# cable-adapter-24.net
KiCad netlist of a schematic drawn in EAGLE
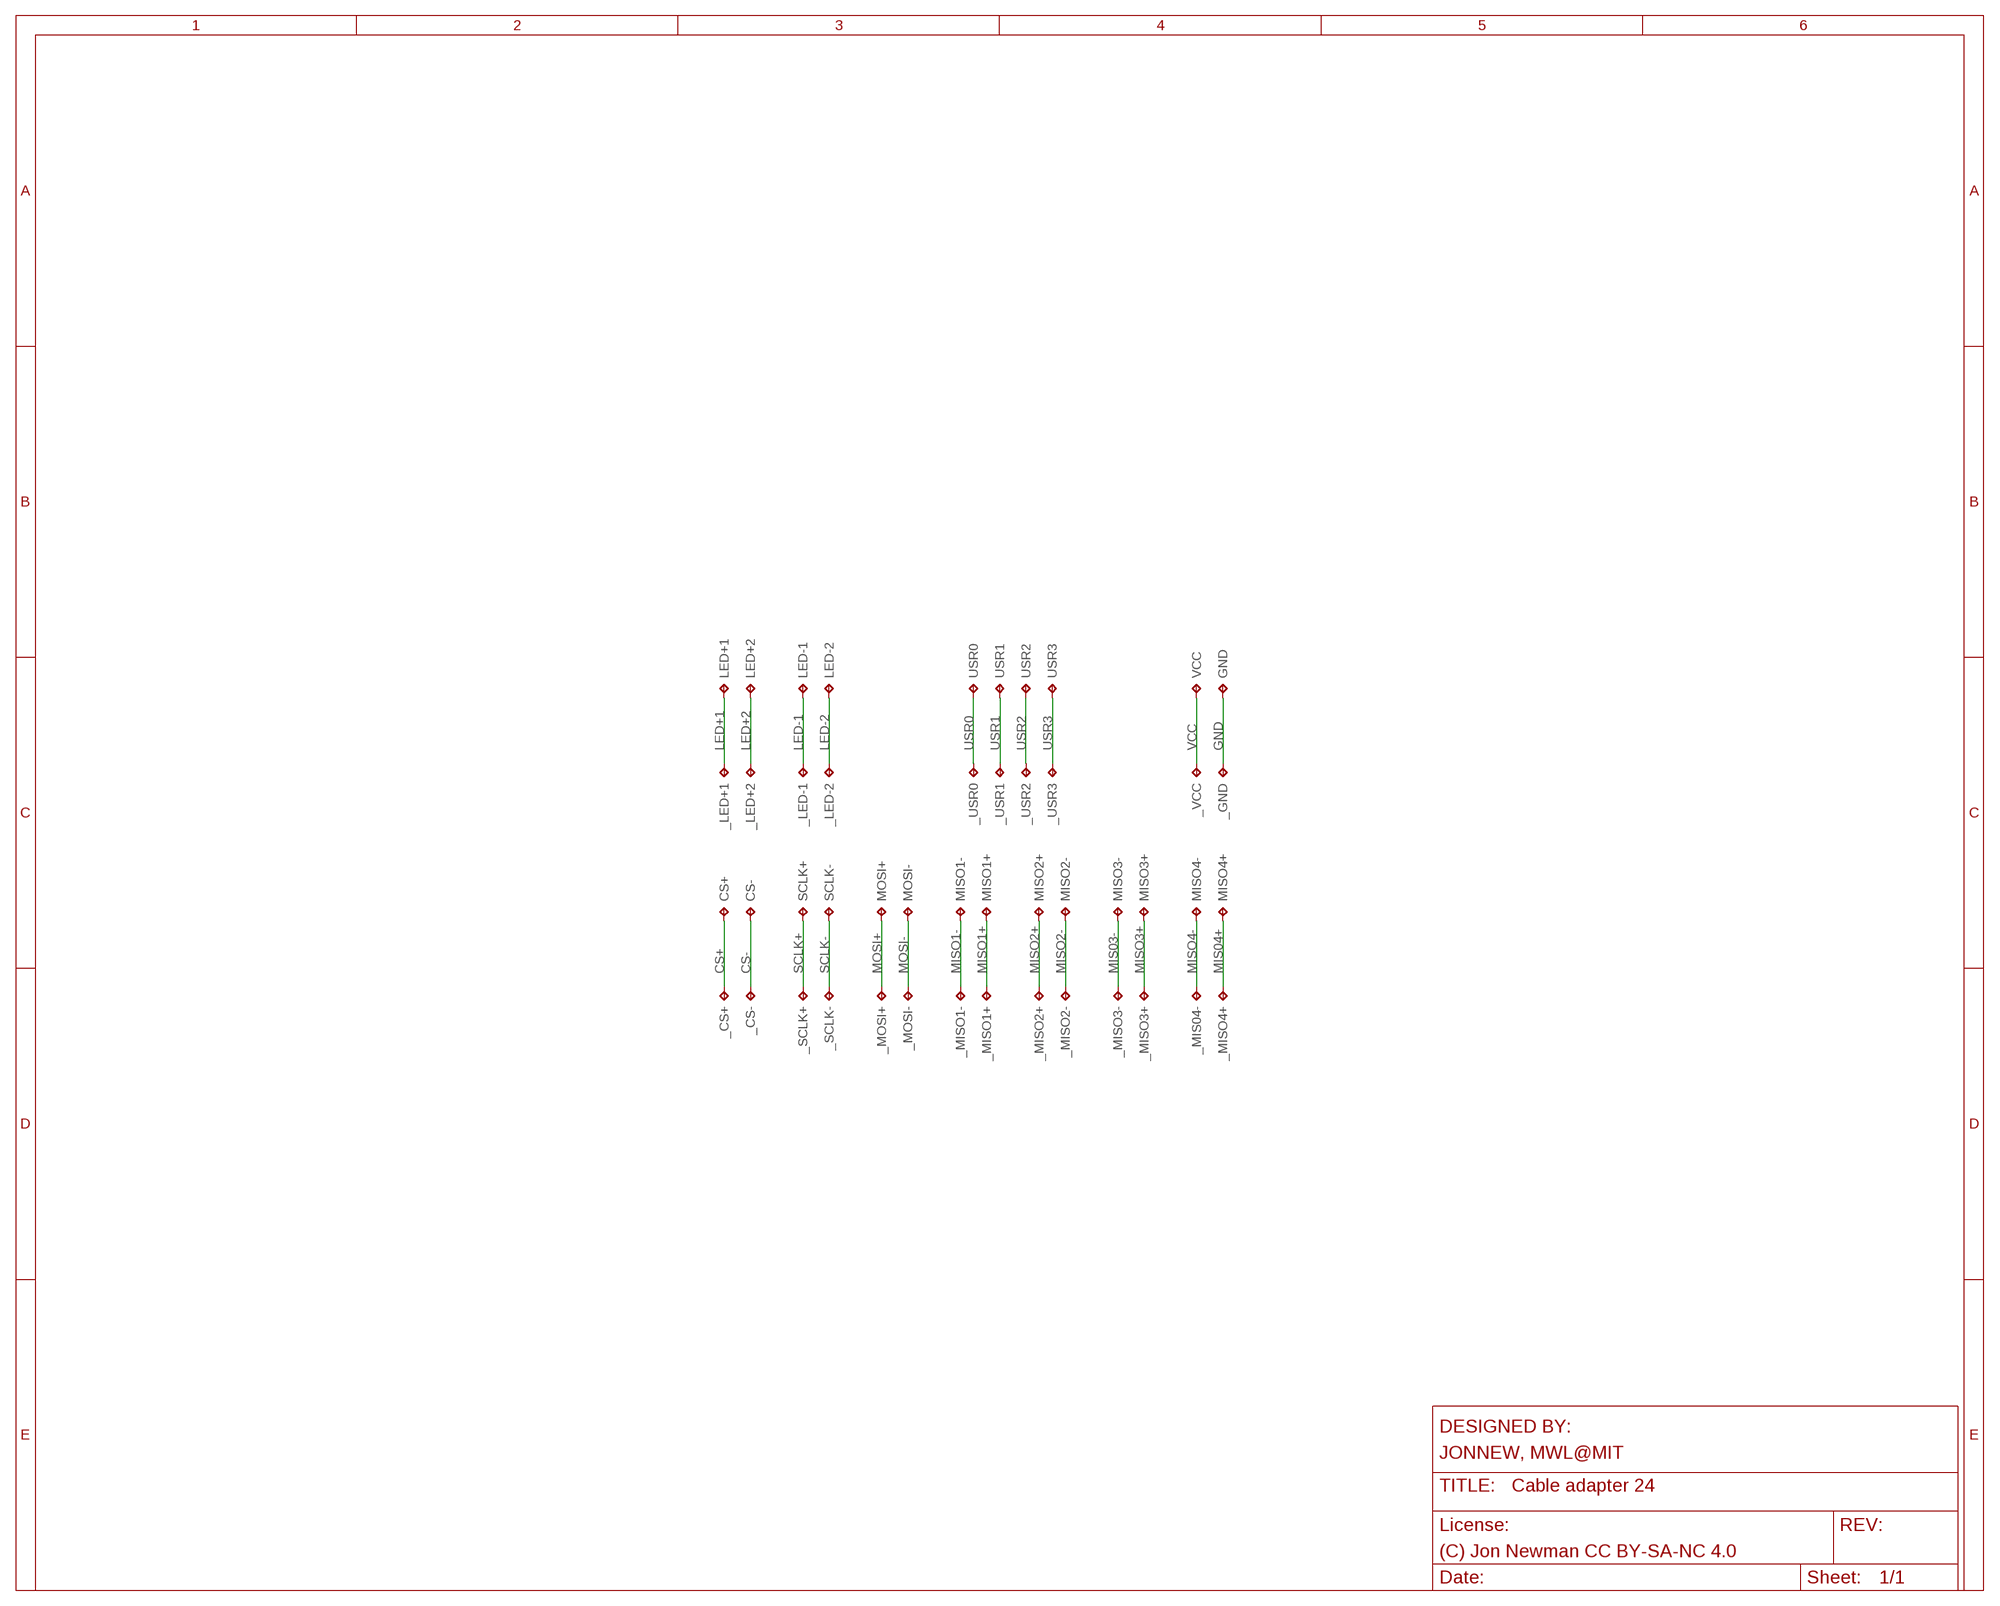
[diagram p0: schematic, sheet 1]

(export (version "E")
  (design (tool "Eeschema 10.0.6"))
  (components
    (comp (ref "CS+")
      (value "TP_SPI_WIRE+")
      (footprint "eagle-import:SPI_WIRE+")
      (libsource (lib "eagle-import") (part "TP_SPI_WIRE+"))
    )
    (comp (ref "CS-")
      (value "TP_SPI_WIRE+")
      (footprint "eagle-import:SPI_WIRE+")
      (libsource (lib "eagle-import") (part "TP_SPI_WIRE+"))
    )
    (comp (ref "GND")
      (value "TP_SPI_WIRE+")
      (footprint "eagle-import:SPI_WIRE+")
      (libsource (lib "eagle-import") (part "TP_SPI_WIRE+"))
    )
    (comp (ref "LED+1")
      (value "TP_SPI_WIRE+")
      (footprint "eagle-import:SPI_WIRE+")
      (libsource (lib "eagle-import") (part "TP_SPI_WIRE+"))
    )
    (comp (ref "LED+2")
      (value "TP_SPI_WIRE+")
      (footprint "eagle-import:SPI_WIRE+")
      (libsource (lib "eagle-import") (part "TP_SPI_WIRE+"))
    )
    (comp (ref "LED-1")
      (value "TP_SPI_WIRE+")
      (footprint "eagle-import:SPI_WIRE+")
      (libsource (lib "eagle-import") (part "TP_SPI_WIRE+"))
    )
    (comp (ref "LED-2")
      (value "TP_SPI_WIRE+")
      (footprint "eagle-import:SPI_WIRE+")
      (libsource (lib "eagle-import") (part "TP_SPI_WIRE+"))
    )
    (comp (ref "MISO1+")
      (value "TP_SPI_WIRE+")
      (footprint "eagle-import:SPI_WIRE+")
      (libsource (lib "eagle-import") (part "TP_SPI_WIRE+"))
    )
    (comp (ref "MISO1-")
      (value "TP_SPI_WIRE+")
      (footprint "eagle-import:SPI_WIRE+")
      (libsource (lib "eagle-import") (part "TP_SPI_WIRE+"))
    )
    (comp (ref "MISO2+")
      (value "TP_SPI_WIRE+")
      (footprint "eagle-import:SPI_WIRE+")
      (libsource (lib "eagle-import") (part "TP_SPI_WIRE+"))
    )
    (comp (ref "MISO2-")
      (value "TP_SPI_WIRE+")
      (footprint "eagle-import:SPI_WIRE+")
      (libsource (lib "eagle-import") (part "TP_SPI_WIRE+"))
    )
    (comp (ref "MISO3+")
      (value "TP_SPI_WIRE+")
      (footprint "eagle-import:SPI_WIRE+")
      (libsource (lib "eagle-import") (part "TP_SPI_WIRE+"))
    )
    (comp (ref "MISO3-")
      (value "TP_SPI_WIRE+")
      (footprint "eagle-import:SPI_WIRE+")
      (libsource (lib "eagle-import") (part "TP_SPI_WIRE+"))
    )
    (comp (ref "MISO4+")
      (value "TP_SPI_WIRE+")
      (footprint "eagle-import:SPI_WIRE+")
      (libsource (lib "eagle-import") (part "TP_SPI_WIRE+"))
    )
    (comp (ref "MISO4-")
      (value "TP_SPI_WIRE+")
      (footprint "eagle-import:SPI_WIRE+")
      (libsource (lib "eagle-import") (part "TP_SPI_WIRE+"))
    )
    (comp (ref "MOSI+")
      (value "TP_SPI_WIRE+")
      (footprint "eagle-import:SPI_WIRE+")
      (libsource (lib "eagle-import") (part "TP_SPI_WIRE+"))
    )
    (comp (ref "MOSI-")
      (value "TP_SPI_WIRE+")
      (footprint "eagle-import:SPI_WIRE+")
      (libsource (lib "eagle-import") (part "TP_SPI_WIRE+"))
    )
    (comp (ref "SCLK+")
      (value "TP_SPI_WIRE+")
      (footprint "eagle-import:SPI_WIRE+")
      (libsource (lib "eagle-import") (part "TP_SPI_WIRE+"))
    )
    (comp (ref "SCLK-")
      (value "TP_SPI_WIRE+")
      (footprint "eagle-import:SPI_WIRE+")
      (libsource (lib "eagle-import") (part "TP_SPI_WIRE+"))
    )
    (comp (ref "USR0")
      (value "TP_SPI_WIRE+")
      (footprint "eagle-import:SPI_WIRE+")
      (libsource (lib "eagle-import") (part "TP_SPI_WIRE+"))
    )
    (comp (ref "USR1")
      (value "TP_SPI_WIRE+")
      (footprint "eagle-import:SPI_WIRE+")
      (libsource (lib "eagle-import") (part "TP_SPI_WIRE+"))
    )
    (comp (ref "USR2")
      (value "TP_SPI_WIRE+")
      (footprint "eagle-import:SPI_WIRE+")
      (libsource (lib "eagle-import") (part "TP_SPI_WIRE+"))
    )
    (comp (ref "USR3")
      (value "TP_SPI_WIRE+")
      (footprint "eagle-import:SPI_WIRE+")
      (libsource (lib "eagle-import") (part "TP_SPI_WIRE+"))
    )
    (comp (ref "VCC")
      (value "TP_SPI_WIRE+")
      (footprint "eagle-import:SPI_WIRE+")
      (libsource (lib "eagle-import") (part "TP_SPI_WIRE+"))
    )
    (comp (ref "_CS+")
      (value "TP_SPI_WIRE+")
      (footprint "eagle-import:SPI_WIRE+")
      (libsource (lib "eagle-import") (part "TP_SPI_WIRE+"))
    )
    (comp (ref "_CS-")
      (value "TP_SPI_WIRE+")
      (footprint "eagle-import:SPI_WIRE+")
      (libsource (lib "eagle-import") (part "TP_SPI_WIRE+"))
    )
    (comp (ref "_GND")
      (value "TP_SPI_WIRE+")
      (footprint "eagle-import:SPI_WIRE+")
      (libsource (lib "eagle-import") (part "TP_SPI_WIRE+"))
    )
    (comp (ref "_LED+1")
      (value "TP_SPI_WIRE+")
      (footprint "eagle-import:SPI_WIRE+")
      (libsource (lib "eagle-import") (part "TP_SPI_WIRE+"))
    )
    (comp (ref "_LED+2")
      (value "TP_SPI_WIRE+")
      (footprint "eagle-import:SPI_WIRE+")
      (libsource (lib "eagle-import") (part "TP_SPI_WIRE+"))
    )
    (comp (ref "_LED-1")
      (value "TP_SPI_WIRE+")
      (footprint "eagle-import:SPI_WIRE+")
      (libsource (lib "eagle-import") (part "TP_SPI_WIRE+"))
    )
    (comp (ref "_LED-2")
      (value "TP_SPI_WIRE+")
      (footprint "eagle-import:SPI_WIRE+")
      (libsource (lib "eagle-import") (part "TP_SPI_WIRE+"))
    )
    (comp (ref "_MIS04-")
      (value "TP_SPI_WIRE+")
      (footprint "eagle-import:SPI_WIRE+")
      (libsource (lib "eagle-import") (part "TP_SPI_WIRE+"))
    )
    (comp (ref "_MISO1+")
      (value "TP_SPI_WIRE+")
      (footprint "eagle-import:SPI_WIRE+")
      (libsource (lib "eagle-import") (part "TP_SPI_WIRE+"))
    )
    (comp (ref "_MISO1-")
      (value "TP_SPI_WIRE+")
      (footprint "eagle-import:SPI_WIRE+")
      (libsource (lib "eagle-import") (part "TP_SPI_WIRE+"))
    )
    (comp (ref "_MISO2+")
      (value "TP_SPI_WIRE+")
      (footprint "eagle-import:SPI_WIRE+")
      (libsource (lib "eagle-import") (part "TP_SPI_WIRE+"))
    )
    (comp (ref "_MISO2-")
      (value "TP_SPI_WIRE+")
      (footprint "eagle-import:SPI_WIRE+")
      (libsource (lib "eagle-import") (part "TP_SPI_WIRE+"))
    )
    (comp (ref "_MISO3+")
      (value "TP_SPI_WIRE+")
      (footprint "eagle-import:SPI_WIRE+")
      (libsource (lib "eagle-import") (part "TP_SPI_WIRE+"))
    )
    (comp (ref "_MISO3-")
      (value "TP_SPI_WIRE+")
      (footprint "eagle-import:SPI_WIRE+")
      (libsource (lib "eagle-import") (part "TP_SPI_WIRE+"))
    )
    (comp (ref "_MISO4+")
      (value "MISO3+")
      (footprint "eagle-import:SPI_WIRE+")
      (libsource (lib "eagle-import") (part "TP_SPI_WIRE+"))
    )
    (comp (ref "_MOSI+")
      (value "TP_SPI_WIRE+")
      (footprint "eagle-import:SPI_WIRE+")
      (libsource (lib "eagle-import") (part "TP_SPI_WIRE+"))
    )
    (comp (ref "_MOSI-")
      (value "TP_SPI_WIRE+")
      (footprint "eagle-import:SPI_WIRE+")
      (libsource (lib "eagle-import") (part "TP_SPI_WIRE+"))
    )
    (comp (ref "_SCLK+")
      (value "TP_SPI_WIRE+")
      (footprint "eagle-import:SPI_WIRE+")
      (libsource (lib "eagle-import") (part "TP_SPI_WIRE+"))
    )
    (comp (ref "_SCLK-")
      (value "TP_SPI_WIRE+")
      (footprint "eagle-import:SPI_WIRE+")
      (libsource (lib "eagle-import") (part "TP_SPI_WIRE+"))
    )
    (comp (ref "_USR0")
      (value "TP_SPI_WIRE+")
      (footprint "eagle-import:SPI_WIRE+")
      (libsource (lib "eagle-import") (part "TP_SPI_WIRE+"))
    )
    (comp (ref "_USR1")
      (value "TP_SPI_WIRE+")
      (footprint "eagle-import:SPI_WIRE+")
      (libsource (lib "eagle-import") (part "TP_SPI_WIRE+"))
    )
    (comp (ref "_USR2")
      (value "TP_SPI_WIRE+")
      (footprint "eagle-import:SPI_WIRE+")
      (libsource (lib "eagle-import") (part "TP_SPI_WIRE+"))
    )
    (comp (ref "_USR3")
      (value "TP_SPI_WIRE+")
      (footprint "eagle-import:SPI_WIRE+")
      (libsource (lib "eagle-import") (part "TP_SPI_WIRE+"))
    )
    (comp (ref "_VCC")
      (value "TP_SPI_WIRE+")
      (footprint "eagle-import:SPI_WIRE+")
      (libsource (lib "eagle-import") (part "TP_SPI_WIRE+"))
    )
  )
  (nets
    (net (code "1") (name "/CS+") (class "Default")
      (node (ref "CS+") (pin "P$1") (pinfunction "TP_P$1") (pintype "input"))
      (node (ref "_CS+") (pin "P$1") (pinfunction "TP_P$1") (pintype "input"))
    )
    (net (code "2") (name "/CS-") (class "Default")
      (node (ref "CS-") (pin "P$1") (pinfunction "TP_P$1") (pintype "input"))
      (node (ref "_CS-") (pin "P$1") (pinfunction "TP_P$1") (pintype "input"))
    )
    (net (code "3") (name "/GND") (class "Default")
      (node (ref "GND") (pin "P$1") (pinfunction "TP_P$1") (pintype "input"))
      (node (ref "_GND") (pin "P$1") (pinfunction "TP_P$1") (pintype "input"))
    )
    (net (code "4") (name "/LED+1") (class "Default")
      (node (ref "LED+1") (pin "P$1") (pinfunction "TP_P$1") (pintype "input"))
      (node (ref "_LED+1") (pin "P$1") (pinfunction "TP_P$1") (pintype "input"))
    )
    (net (code "5") (name "/LED+2") (class "Default")
      (node (ref "LED+2") (pin "P$1") (pinfunction "TP_P$1") (pintype "input"))
      (node (ref "_LED+2") (pin "P$1") (pinfunction "TP_P$1") (pintype "input"))
    )
    (net (code "6") (name "/LED-1") (class "Default")
      (node (ref "LED-1") (pin "P$1") (pinfunction "TP_P$1") (pintype "input"))
      (node (ref "_LED-1") (pin "P$1") (pinfunction "TP_P$1") (pintype "input"))
    )
    (net (code "7") (name "/LED-2") (class "Default")
      (node (ref "LED-2") (pin "P$1") (pinfunction "TP_P$1") (pintype "input"))
      (node (ref "_LED-2") (pin "P$1") (pinfunction "TP_P$1") (pintype "input"))
    )
    (net (code "8") (name "/MIS03-") (class "Default")
      (node (ref "MISO3-") (pin "P$1") (pinfunction "TP_P$1") (pintype "input"))
      (node (ref "_MISO3-") (pin "P$1") (pinfunction "TP_P$1") (pintype "input"))
    )
    (net (code "9") (name "/MIS04+") (class "Default")
      (node (ref "MISO4+") (pin "P$1") (pinfunction "TP_P$1") (pintype "input"))
      (node (ref "_MISO4+") (pin "P$1") (pinfunction "TP_P$1") (pintype "input"))
    )
    (net (code "10") (name "/MISO1+") (class "Default")
      (node (ref "MISO1+") (pin "P$1") (pinfunction "TP_P$1") (pintype "input"))
      (node (ref "_MISO1+") (pin "P$1") (pinfunction "TP_P$1") (pintype "input"))
    )
    (net (code "11") (name "/MISO1-") (class "Default")
      (node (ref "MISO1-") (pin "P$1") (pinfunction "TP_P$1") (pintype "input"))
      (node (ref "_MISO1-") (pin "P$1") (pinfunction "TP_P$1") (pintype "input"))
    )
    (net (code "12") (name "/MISO2+") (class "Default")
      (node (ref "MISO2+") (pin "P$1") (pinfunction "TP_P$1") (pintype "input"))
      (node (ref "_MISO2+") (pin "P$1") (pinfunction "TP_P$1") (pintype "input"))
    )
    (net (code "13") (name "/MISO2-") (class "Default")
      (node (ref "MISO2-") (pin "P$1") (pinfunction "TP_P$1") (pintype "input"))
      (node (ref "_MISO2-") (pin "P$1") (pinfunction "TP_P$1") (pintype "input"))
    )
    (net (code "14") (name "/MISO3+") (class "Default")
      (node (ref "MISO3+") (pin "P$1") (pinfunction "TP_P$1") (pintype "input"))
      (node (ref "_MISO3+") (pin "P$1") (pinfunction "TP_P$1") (pintype "input"))
    )
    (net (code "15") (name "/MISO4-") (class "Default")
      (node (ref "MISO4-") (pin "P$1") (pinfunction "TP_P$1") (pintype "input"))
      (node (ref "_MIS04-") (pin "P$1") (pinfunction "TP_P$1") (pintype "input"))
    )
    (net (code "16") (name "/MOSI+") (class "Default")
      (node (ref "MOSI+") (pin "P$1") (pinfunction "TP_P$1") (pintype "input"))
      (node (ref "_MOSI+") (pin "P$1") (pinfunction "TP_P$1") (pintype "input"))
    )
    (net (code "17") (name "/MOSI-") (class "Default")
      (node (ref "MOSI-") (pin "P$1") (pinfunction "TP_P$1") (pintype "input"))
      (node (ref "_MOSI-") (pin "P$1") (pinfunction "TP_P$1") (pintype "input"))
    )
    (net (code "18") (name "/SCLK+") (class "Default")
      (node (ref "SCLK+") (pin "P$1") (pinfunction "TP_P$1") (pintype "input"))
      (node (ref "_SCLK+") (pin "P$1") (pinfunction "TP_P$1") (pintype "input"))
    )
    (net (code "19") (name "/SCLK-") (class "Default")
      (node (ref "SCLK-") (pin "P$1") (pinfunction "TP_P$1") (pintype "input"))
      (node (ref "_SCLK-") (pin "P$1") (pinfunction "TP_P$1") (pintype "input"))
    )
    (net (code "20") (name "/USR0") (class "Default")
      (node (ref "USR0") (pin "P$1") (pinfunction "TP_P$1") (pintype "input"))
      (node (ref "_USR0") (pin "P$1") (pinfunction "TP_P$1") (pintype "input"))
    )
    (net (code "21") (name "/USR1") (class "Default")
      (node (ref "USR1") (pin "P$1") (pinfunction "TP_P$1") (pintype "input"))
      (node (ref "_USR1") (pin "P$1") (pinfunction "TP_P$1") (pintype "input"))
    )
    (net (code "22") (name "/USR2") (class "Default")
      (node (ref "USR2") (pin "P$1") (pinfunction "TP_P$1") (pintype "input"))
      (node (ref "_USR2") (pin "P$1") (pinfunction "TP_P$1") (pintype "input"))
    )
    (net (code "23") (name "/USR3") (class "Default")
      (node (ref "USR3") (pin "P$1") (pinfunction "TP_P$1") (pintype "input"))
      (node (ref "_USR3") (pin "P$1") (pinfunction "TP_P$1") (pintype "input"))
    )
    (net (code "24") (name "/VCC") (class "Default")
      (node (ref "VCC") (pin "P$1") (pinfunction "TP_P$1") (pintype "input"))
      (node (ref "_VCC") (pin "P$1") (pinfunction "TP_P$1") (pintype "input"))
    )
  )
)
